# hw-demo02.net
KiCad netlist of a schematic drawn in EAGLE
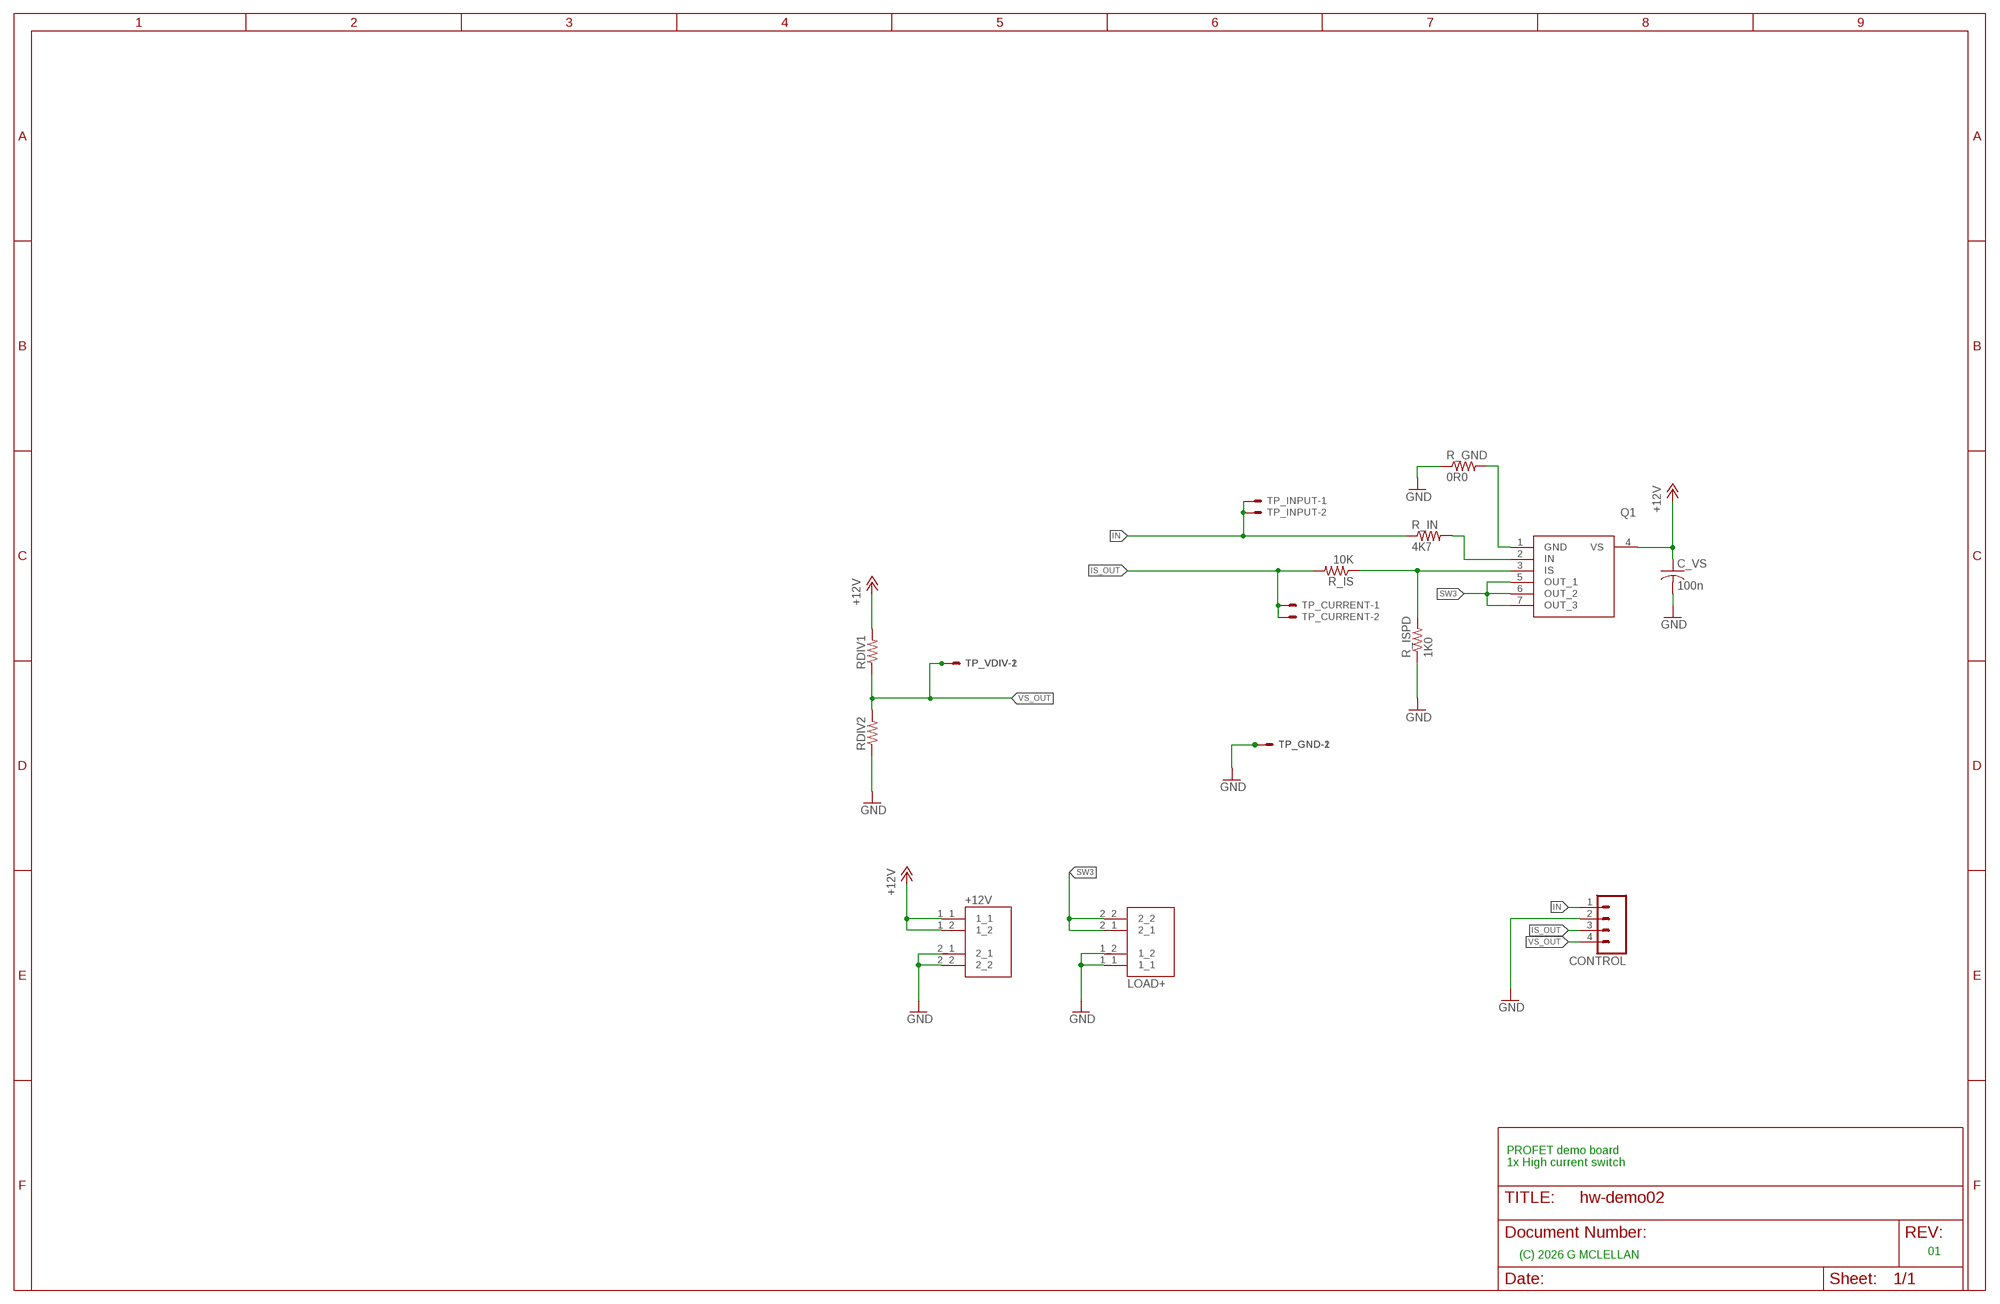
[diagram p0: schematic, sheet 1]

(export (version "E")
  (design (tool "Eeschema 10.0.6"))
  (components
    (comp (ref "+12V")
      (value "VP0265840000G")
      (footprint "eagle-import:AMPHENOL_VP0265840000G")
      (fields (field (name "MANUFACTURER") "Amphenol Anytek"))
      (libsource (lib "eagle-import") (part "VP0265840000G"))
    )
    (comp (ref "CONTROL")
      (value "M04LOCK")
      (footprint "eagle-import:1X04_LOCK")
      (libsource (lib "eagle-import") (part "M04LOCK"))
    )
    (comp (ref "C_VS")
      (value "100n")
      (footprint "eagle-import:C0805K")
      (libsource (lib "eagle-import") (part "C-USC0805K"))
    )
    (comp (ref "LOAD+")
      (value "VP0265840000G")
      (footprint "eagle-import:AMPHENOL_VP0265840000G")
      (fields (field (name "MANUFACTURER") "Amphenol Anytek"))
      (libsource (lib "eagle-import") (part "VP0265840000G"))
    )
    (comp (ref "Q1")
      (value "BTS500101TADATMA2")
      (footprint "eagle-import:BTS500101TADATMA2")
      (fields (field (name "MOUSER_PART_NUMBER") "726-BTS500101TADATM2"))
      (libsource (lib "eagle-import") (part "BTS500101TADATMA2"))
    )
    (comp (ref "RDIV1")
      (value "R-US_R0805")
      (footprint "eagle-import:R0805")
      (libsource (lib "eagle-import") (part "R-US_R0805"))
    )
    (comp (ref "RDIV2")
      (value "R-US_R0805")
      (footprint "eagle-import:R0805")
      (libsource (lib "eagle-import") (part "R-US_R0805"))
    )
    (comp (ref "R_GND")
      (value "0R0")
      (footprint "eagle-import:R1206W")
      (libsource (lib "eagle-import") (part "R-US_R1206W"))
    )
    (comp (ref "R_IN")
      (value "4K7")
      (footprint "eagle-import:0207_12")
      (libsource (lib "eagle-import") (part "R-US_0207/12"))
    )
    (comp (ref "R_IS")
      (value "10K")
      (footprint "eagle-import:0207_12")
      (libsource (lib "eagle-import") (part "R-US_0207/12"))
    )
    (comp (ref "R_ISPD")
      (value "1K0")
      (footprint "eagle-import:0207_12")
      (libsource (lib "eagle-import") (part "R-US_0207/12"))
    )
    (comp (ref "TP_CURRENT")
      (value "22-23-2021")
      (footprint "eagle-import:22-23-2021")
      (fields (field (name "MF") "MOLEX"))
      (libsource (lib "eagle-import") (part "22-23-2021"))
    )
    (comp (ref "TP_GND")
      (value "22-23-2021")
      (footprint "eagle-import:22-23-2021")
      (fields (field (name "MF") "MOLEX"))
      (libsource (lib "eagle-import") (part "22-23-2021"))
    )
    (comp (ref "TP_INPUT")
      (value "22-23-2021")
      (footprint "eagle-import:22-23-2021")
      (fields (field (name "MF") "MOLEX"))
      (libsource (lib "eagle-import") (part "22-23-2021"))
    )
    (comp (ref "TP_VDIV")
      (value "22-23-2021")
      (footprint "eagle-import:22-23-2021")
      (fields (field (name "MF") "MOLEX"))
      (libsource (lib "eagle-import") (part "22-23-2021"))
    )
  )
  (nets
    (net (code "1") (name "+12V") (class "Default")
      (node (ref "+12V") (pin "1_1") (pinfunction "1_1_1_1") (pintype "passive"))
      (node (ref "+12V") (pin "1_2") (pinfunction "1_2_1_2") (pintype "passive"))
      (node (ref "C_VS") (pin "1") (pinfunction "1_1") (pintype "passive"))
      (node (ref "Q1") (pin "4") (pinfunction "VS_4") (pintype "bidirectional"))
      (node (ref "RDIV1") (pin "2") (pinfunction "2_2") (pintype "passive"))
    )
    (net (code "2") (name "GND") (class "Default")
      (node (ref "+12V") (pin "2_1") (pinfunction "2_1_2_1") (pintype "passive"))
      (node (ref "+12V") (pin "2_2") (pinfunction "2_2_2_2") (pintype "passive"))
      (node (ref "CONTROL") (pin "2") (pinfunction "2_2") (pintype "passive"))
      (node (ref "C_VS") (pin "2") (pinfunction "2_2") (pintype "passive"))
      (node (ref "LOAD+") (pin "1_1") (pinfunction "1_1_1_1") (pintype "passive"))
      (node (ref "LOAD+") (pin "1_2") (pinfunction "1_2_1_2") (pintype "passive"))
      (node (ref "RDIV2") (pin "1") (pinfunction "1_1") (pintype "passive"))
      (node (ref "R_GND") (pin "1") (pinfunction "1_1") (pintype "passive"))
      (node (ref "R_ISPD") (pin "1") (pinfunction "1_1") (pintype "passive"))
      (node (ref "TP_GND") (pin "1") (pinfunction "S_1") (pintype "passive"))
      (node (ref "TP_GND") (pin "2") (pinfunction "S_2") (pintype "passive"))
    )
    (net (code "3") (name "IN") (class "Default")
      (node (ref "CONTROL") (pin "1") (pinfunction "1_1") (pintype "passive"))
      (node (ref "R_IN") (pin "1") (pinfunction "1_1") (pintype "passive"))
      (node (ref "TP_INPUT") (pin "1") (pinfunction "S_1") (pintype "passive"))
      (node (ref "TP_INPUT") (pin "2") (pinfunction "S_2") (pintype "passive"))
    )
    (net (code "4") (name "IS_OUT") (class "Default")
      (node (ref "CONTROL") (pin "3") (pinfunction "3_3") (pintype "passive"))
      (node (ref "R_IS") (pin "2") (pinfunction "2_2") (pintype "passive"))
      (node (ref "TP_CURRENT") (pin "1") (pinfunction "S_1") (pintype "passive"))
      (node (ref "TP_CURRENT") (pin "2") (pinfunction "S_2") (pintype "passive"))
    )
    (net (code "5") (name "Net-(Q1-GND)") (class "Default")
      (node (ref "Q1") (pin "1") (pinfunction "GND_1") (pintype "bidirectional"))
      (node (ref "R_GND") (pin "2") (pinfunction "2_2") (pintype "passive"))
    )
    (net (code "6") (name "Net-(Q1-IN)") (class "Default")
      (node (ref "Q1") (pin "2") (pinfunction "IN_2") (pintype "bidirectional"))
      (node (ref "R_IN") (pin "2") (pinfunction "2_2") (pintype "passive"))
    )
    (net (code "7") (name "Net-(Q1-IS)") (class "Default")
      (node (ref "Q1") (pin "3") (pinfunction "IS_3") (pintype "bidirectional"))
      (node (ref "R_IS") (pin "1") (pinfunction "1_1") (pintype "passive"))
      (node (ref "R_ISPD") (pin "2") (pinfunction "2_2") (pintype "passive"))
    )
    (net (code "8") (name "SW3") (class "Default")
      (node (ref "LOAD+") (pin "2_1") (pinfunction "2_1_2_1") (pintype "passive"))
      (node (ref "LOAD+") (pin "2_2") (pinfunction "2_2_2_2") (pintype "passive"))
      (node (ref "Q1") (pin "5") (pinfunction "OUT_1_5") (pintype "bidirectional"))
      (node (ref "Q1") (pin "6") (pinfunction "OUT_2_6") (pintype "bidirectional"))
      (node (ref "Q1") (pin "7") (pinfunction "OUT_3_7") (pintype "bidirectional"))
    )
    (net (code "9") (name "VS_OUT") (class "Default")
      (node (ref "CONTROL") (pin "4") (pinfunction "4_4") (pintype "passive"))
      (node (ref "RDIV1") (pin "1") (pinfunction "1_1") (pintype "passive"))
      (node (ref "RDIV2") (pin "2") (pinfunction "2_2") (pintype "passive"))
      (node (ref "TP_VDIV") (pin "1") (pinfunction "S_1") (pintype "passive"))
      (node (ref "TP_VDIV") (pin "2") (pinfunction "S_2") (pintype "passive"))
    )
  )
)
